# 2001A.net
KiCad netlist of a schematic drawn in Altium Designer
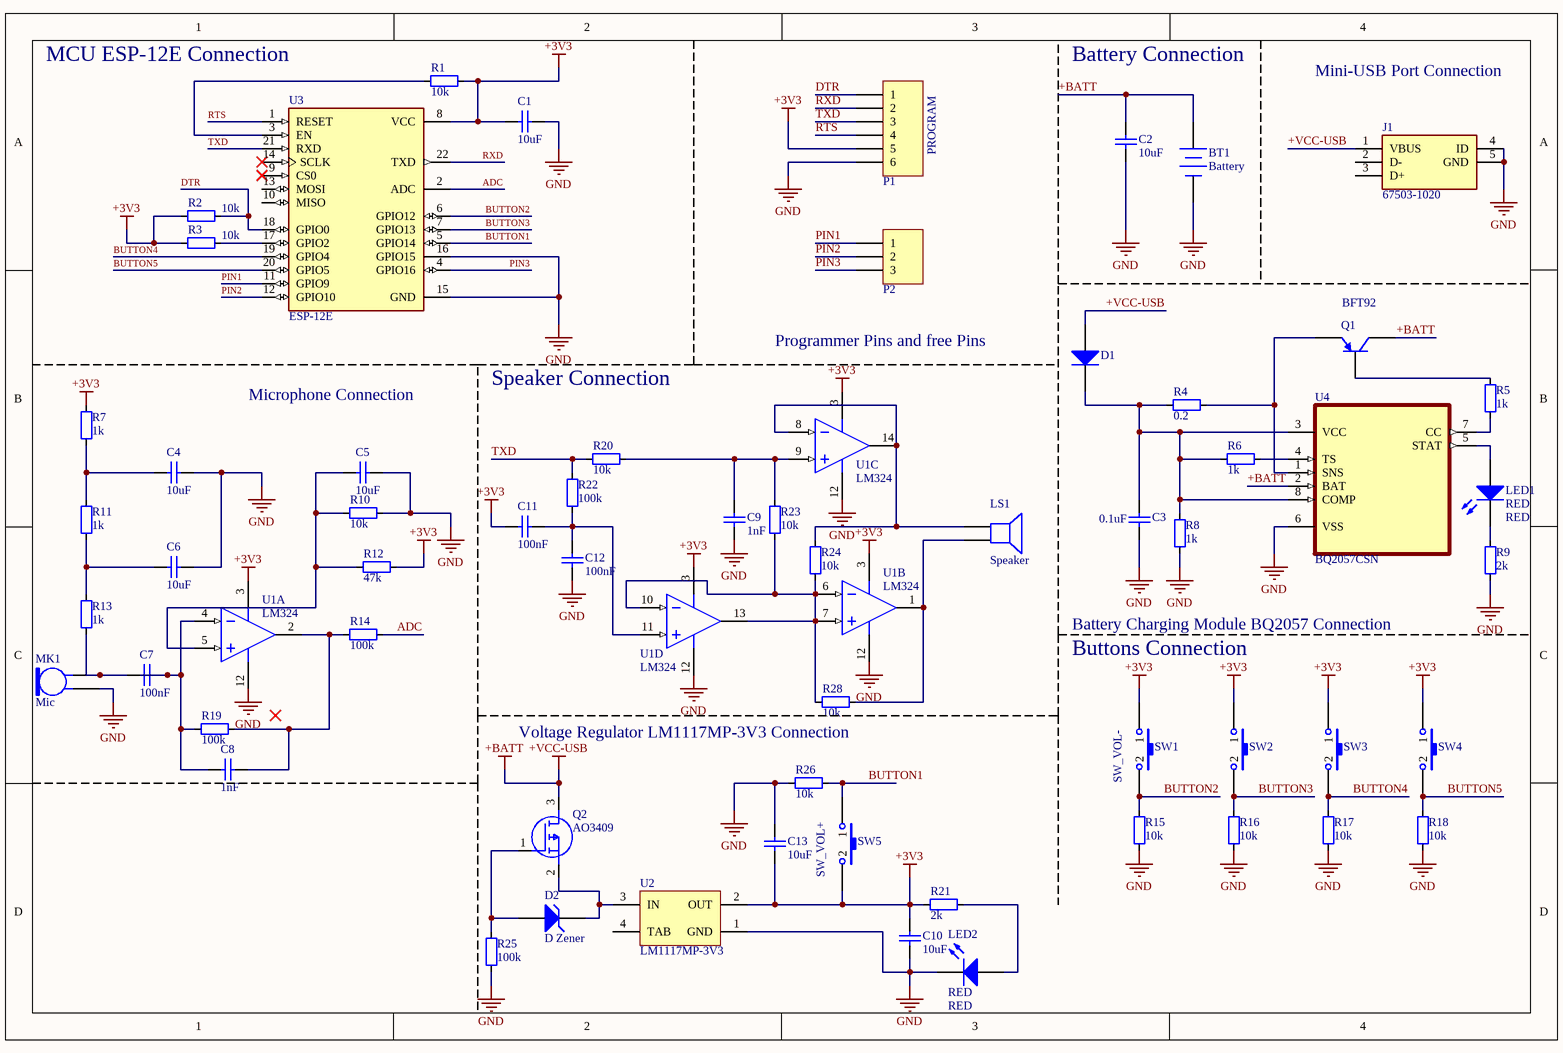
[diagram p0: 2001A.SchDoc]

(export (version "E")
  (design (tool "Eeschema 10.0.6"))
  (components
    (comp (ref "BT1")
      (value "Battery")
      (footprint "BAT-2")
      (description "Multicell Battery")
      (fields (field (name "PUBLISHER") "Altium Limited"))
      (libsource (lib "Miscellaneous Devices") (part "Battery"))
    )
    (comp (ref "C1")
      (value "10uF")
      (footprint "0603_CAP")
      (description "Ceramic capacitor")
      (fields (field (name "Comment") "Cap"))
      (libsource (lib "biblioteka_schematic") (part "Cap"))
    )
    (comp (ref "C2")
      (value "10uF")
      (footprint "0603_CAP")
      (description "Ceramic capacitor")
      (fields (field (name "Comment") "Cap"))
      (libsource (lib "biblioteka_schematic") (part "Cap"))
    )
    (comp (ref "C3")
      (value "0.1uF")
      (footprint "0603_CAP")
      (description "Ceramic capacitor")
      (fields (field (name "Comment") "Cap"))
      (libsource (lib "biblioteka_schematic") (part "Cap"))
    )
    (comp (ref "C4")
      (value "10uF")
      (footprint "0603_CAP")
      (description "Ceramic capacitor")
      (fields (field (name "Comment") "Cap"))
      (libsource (lib "biblioteka_schematic") (part "Cap"))
    )
    (comp (ref "C5")
      (value "10uF")
      (footprint "0603_CAP")
      (description "Ceramic capacitor")
      (fields (field (name "Comment") "Cap"))
      (libsource (lib "biblioteka_schematic") (part "Cap"))
    )
    (comp (ref "C6")
      (value "10uF")
      (footprint "0603_CAP")
      (description "Ceramic capacitor")
      (fields (field (name "Comment") "Cap"))
      (libsource (lib "biblioteka_schematic") (part "Cap"))
    )
    (comp (ref "C7")
      (value "100nF")
      (footprint "0603_CAP")
      (description "Ceramic capacitor")
      (fields (field (name "Comment") "Cap"))
      (libsource (lib "biblioteka_schematic") (part "Cap"))
    )
    (comp (ref "C8")
      (value "1nF")
      (footprint "0603_CAP")
      (description "Ceramic capacitor")
      (fields (field (name "Comment") "Cap"))
      (libsource (lib "biblioteka_schematic") (part "Cap"))
    )
    (comp (ref "C9")
      (value "1nF")
      (footprint "0603_CAP")
      (description "Ceramic capacitor")
      (fields (field (name "Comment") "Cap"))
      (libsource (lib "biblioteka_schematic") (part "Cap"))
    )
    (comp (ref "C10")
      (value "10uF")
      (footprint "0603_CAP")
      (description "Ceramic capacitor")
      (fields (field (name "Comment") "Cap"))
      (libsource (lib "biblioteka_schematic") (part "Cap"))
    )
    (comp (ref "C11")
      (value "100nF")
      (footprint "0603_CAP")
      (description "Ceramic capacitor")
      (fields (field (name "Comment") "Cap"))
      (libsource (lib "biblioteka_schematic") (part "Cap"))
    )
    (comp (ref "C12")
      (value "100nF")
      (footprint "0603_CAP")
      (description "Ceramic capacitor")
      (fields (field (name "Comment") "Cap"))
      (libsource (lib "biblioteka_schematic") (part "Cap"))
    )
    (comp (ref "C13")
      (value "10uF")
      (footprint "0603_CAP")
      (description "Ceramic capacitor")
      (fields (field (name "Comment") "Cap"))
      (libsource (lib "biblioteka_schematic") (part "Cap"))
    )
    (comp (ref "D1")
      (value "~")
      (footprint "0805_DIODE")
      (description "High-speed diode")
      (libsource (lib "biblioteka_schematic") (part "1N4148"))
    )
    (comp (ref "D2")
      (value "D Zener")
      (footprint "*SOD-123_2_BZT52C4V7(Primary)")
      (description "Zener Diode")
      (fields (field (name "PUBLISHER") "Altium Limited"))
      (libsource (lib "Miscellaneous Devices") (part "D Zener"))
    )
    (comp (ref "ESP-12E")
      (value "U3")
      (footprint "XCVR_ESP8266-12E/ESP-12E")
      (fields (field (name "MP") "ESP8266-12E/ESP-12E") (field (name "MF") "AI-Thinker"))
      (libsource (lib "SnapEDAsch") (part "ESP8266-12E/ESP-12E"))
    )
    (comp (ref "J1")
      (value "67503-1020")
      (footprint "SamacSys:67503-1020")
      (description "Connector")
      (fields (field (name "MOUSER PART NUMBER") "538-67503-1020") (field (name "RS PART NUMBER") "1891440"))
      (libsource (lib "usb_otg") (part "67503-1020"))
    )
    (comp (ref "LED1")
      (value "RED")
      (footprint "LED_THT_RED")
      (description "Light-emitting diode")
      (fields (field (name "COLOR") "RED"))
      (libsource (lib "biblioteka_schematic") (part "LED"))
    )
    (comp (ref "LED2")
      (value "RED")
      (footprint "0603")
      (description "Light-emitting diode")
      (fields (field (name "COLOR") "RED"))
      (libsource (lib "biblioteka_schematic") (part "LED"))
    )
    (comp (ref "LS1")
      (value "Speaker")
      (footprint "PIN2")
      (description "Loudspeaker")
      (fields (field (name "PUBLISHER") "Altium Limited"))
      (libsource (lib "Miscellaneous Devices") (part "Speaker"))
    )
    (comp (ref "MK1")
      (value "Mic")
      (footprint "PIN2")
      (description "Microphone")
      (fields (field (name "PUBLISHER") "Altium Limited"))
      (libsource (lib "Miscellaneous Devices") (part "Mic2"))
    )
    (comp (ref "P1")
      (value "PROGRAM")
      (footprint "HDR1X6")
      (description "Header, 6-Pin")
      (fields (field (name "PUBLISHER") "Altium Limited"))
      (libsource (lib "biblioteka_schematic") (part "HDR1X6"))
    )
    (comp (ref "P2")
      (value "HDR1X3")
      (footprint "HDR1X3")
      (description "Header, 3-Pin")
      (fields (field (name "PUBLISHER") "Altium Limited"))
      (libsource (lib "biblioteka_schematic") (part "HDR1X3"))
    )
    (comp (ref "Q1")
      (value "BFT92")
      (footprint "SOT23-3")
      (description "PNP General Purpose Amplifier")
      (fields (field (name "PUBLISHER") "Altium Limited"))
      (libsource (lib "Miscellaneous Devices") (part "2N3906"))
    )
    (comp (ref "Q2")
      (value "AO3409")
      (footprint "SamacSys:SOT95P237X112-3N")
      (description "MOSFET (P-Channel)")
      (fields
        (field (name "MANUFACTURER_PART_NUMBER") "FDN340P")
        (field (name "MOUSER PART NUMBER") "512-FDN340P")
      )
      (libsource (lib "*") (part "FDN340P"))
    )
    (comp (ref "R1")
      (value "10k")
      (footprint "0603")
      (description "Resistior")
      (libsource (lib "") (part "RES_1"))
    )
    (comp (ref "R2")
      (value "10k")
      (footprint "0603")
      (description "Resistior")
      (libsource (lib "") (part "RES_1"))
    )
    (comp (ref "R3")
      (value "10k")
      (footprint "0603")
      (description "Resistior")
      (libsource (lib "") (part "RES_1"))
    )
    (comp (ref "R4")
      (value "0.2")
      (footprint "0805")
      (description "Resistior")
      (libsource (lib "") (part "RES_1"))
    )
    (comp (ref "R5")
      (value "1k")
      (footprint "0603")
      (description "Resistior")
      (libsource (lib "biblioteka_schematic") (part "RES"))
    )
    (comp (ref "R6")
      (value "1k")
      (footprint "0603")
      (description "Resistior")
      (libsource (lib "") (part "RES_1"))
    )
    (comp (ref "R7")
      (value "1k")
      (footprint "0603")
      (description "Resistior")
      (libsource (lib "biblioteka_schematic") (part "RES"))
    )
    (comp (ref "R8")
      (value "1k")
      (footprint "0603")
      (description "Resistior")
      (libsource (lib "biblioteka_schematic") (part "RES"))
    )
    (comp (ref "R9")
      (value "2k")
      (footprint "0603")
      (description "Resistior")
      (libsource (lib "biblioteka_schematic") (part "RES"))
    )
    (comp (ref "R10")
      (value "10k")
      (footprint "0603")
      (description "Resistior")
      (libsource (lib "") (part "RES_1"))
    )
    (comp (ref "R11")
      (value "1k")
      (footprint "0603")
      (description "Resistior")
      (libsource (lib "biblioteka_schematic") (part "RES"))
    )
    (comp (ref "R12")
      (value "47k")
      (footprint "0603")
      (description "Resistior")
      (libsource (lib "") (part "RES_1"))
    )
    (comp (ref "R13")
      (value "1k")
      (footprint "0603")
      (description "Resistior")
      (libsource (lib "biblioteka_schematic") (part "RES"))
    )
    (comp (ref "R14")
      (value "100k")
      (footprint "0603")
      (description "Resistior")
      (libsource (lib "") (part "RES_1"))
    )
    (comp (ref "R15")
      (value "10k")
      (footprint "0603")
      (description "Resistior")
      (libsource (lib "biblioteka_schematic") (part "RES"))
    )
    (comp (ref "R16")
      (value "10k")
      (footprint "0603")
      (description "Resistior")
      (libsource (lib "biblioteka_schematic") (part "RES"))
    )
    (comp (ref "R17")
      (value "10k")
      (footprint "0603")
      (description "Resistior")
      (libsource (lib "biblioteka_schematic") (part "RES"))
    )
    (comp (ref "R18")
      (value "10k")
      (footprint "0603")
      (description "Resistior")
      (libsource (lib "biblioteka_schematic") (part "RES"))
    )
    (comp (ref "R19")
      (value "100k")
      (footprint "0603")
      (description "Resistior")
      (libsource (lib "") (part "RES_1"))
    )
    (comp (ref "R20")
      (value "10k")
      (footprint "0603")
      (description "Resistior")
      (libsource (lib "") (part "RES_1"))
    )
    (comp (ref "R21")
      (value "2k")
      (footprint "0603")
      (description "Resistior")
      (libsource (lib "") (part "RES_3"))
    )
    (comp (ref "R22")
      (value "100k")
      (footprint "0603")
      (description "Resistior")
      (libsource (lib "") (part "RES_2"))
    )
    (comp (ref "R23")
      (value "10k")
      (footprint "0603")
      (description "Resistior")
      (libsource (lib "") (part "RES_2"))
    )
    (comp (ref "R24")
      (value "10k")
      (footprint "0603")
      (description "Resistior")
      (libsource (lib "") (part "RES_2"))
    )
    (comp (ref "R25")
      (value "100k")
      (footprint "0603")
      (description "Resistior")
      (libsource (lib "biblioteka_schematic") (part "RES"))
    )
    (comp (ref "R26")
      (value "10k")
      (footprint "0603")
      (description "Resistior")
      (libsource (lib "") (part "RES_3"))
    )
    (comp (ref "R28")
      (value "10k")
      (footprint "0603")
      (description "Resistior")
      (libsource (lib "") (part "RES_1"))
    )
    (comp (ref "SW1")
      (value "SW_VOL-")
      (footprint "Micro_Switch")
      (description "Switch")
      (fields (field (name "PUBLISHER") "Altium Limited"))
      (libsource (lib "biblioteka_schematic") (part "Micro_Switch"))
    )
    (comp (ref "SW2")
      (value "SW_VOL-")
      (footprint "Micro_Switch")
      (description "Switch")
      (fields (field (name "PUBLISHER") "Altium Limited"))
      (libsource (lib "biblioteka_schematic") (part "Micro_Switch"))
    )
    (comp (ref "SW3")
      (value "SW_VOL-")
      (footprint "Micro_Switch")
      (description "Switch")
      (fields (field (name "PUBLISHER") "Altium Limited"))
      (libsource (lib "biblioteka_schematic") (part "Micro_Switch"))
    )
    (comp (ref "SW4")
      (value "SW_VOL-")
      (footprint "Micro_Switch")
      (description "Switch")
      (fields (field (name "PUBLISHER") "Altium Limited"))
      (libsource (lib "biblioteka_schematic") (part "Micro_Switch"))
    )
    (comp (ref "SW5")
      (value "SW_VOL+")
      (footprint "Micro_Switch")
      (description "Switch")
      (fields (field (name "PUBLISHER") "Altium Limited"))
      (libsource (lib "biblioteka_schematic") (part "Micro_Switch"))
    )
    (comp (ref "U1")
      (value "LM324")
      (footprint "SOIC14")
      (description "Quad Single-Supply Comparator")
      (fields (field (name "PUBLISHER") "Altium Limited"))
      (libsource (lib "biblioteka_schematic") (part "LM339AD"))
    )
    (comp (ref "U2")
      (value "LM1117MP-3V3")
      (footprint "SOT223")
      (description "800mA Low-Dropout Linear Regulator")
      (fields
        (field (name "PARTNUMBER") "LM1117MP-3.3")
        (field (name "MANUFACTURER") "National Semiconductor")
        (field (name "PUBLISHER") "Altium Limited")
      )
      (libsource (lib "biblioteka_schematic") (part "LM1117MP-3V3"))
    )
    (comp (ref "U4")
      (value "BQ2057CSN")
      (footprint "SOIC127P600X175-14N")
      (description "Charger IC Lithium Ion/Polymer 8-SOIC")
      (fields (field (name "MF") "Texas Instruments"))
      (libsource (lib "BQ2057CSN") (part "BQ2057CSN"))
    )
  )
  (nets
    (net (code "1") (name "+3V3") (class "Default")
      (node (ref "C1") (pin "1") (pinfunction "1_1") (pintype "passive"))
      (node (ref "C10") (pin "2") (pinfunction "2_2") (pintype "passive"))
      (node (ref "C11") (pin "1") (pinfunction "1_1") (pintype "passive"))
      (node (ref "C13") (pin "1") (pinfunction "1_1") (pintype "passive"))
      (node (ref "ESP-12E") (pin "8") (pinfunction "VCC_8") (pintype "power_in"))
      (node (ref "P1") (pin "5") (pinfunction "5_5") (pintype "passive"))
      (node (ref "R1") (pin "2") (pinfunction "2_2") (pintype "passive"))
      (node (ref "R12") (pin "2") (pinfunction "2_2") (pintype "passive"))
      (node (ref "R2") (pin "1") (pinfunction "1_1") (pintype "passive"))
      (node (ref "R21") (pin "2") (pinfunction "2_2") (pintype "passive"))
      (node (ref "R3") (pin "1") (pinfunction "1_1") (pintype "passive"))
      (node (ref "R7") (pin "1") (pinfunction "1_1") (pintype "passive"))
      (node (ref "SW1") (pin "1") (pinfunction "1_1") (pintype "passive"))
      (node (ref "SW2") (pin "1") (pinfunction "1_1") (pintype "passive"))
      (node (ref "SW3") (pin "1") (pinfunction "1_1") (pintype "passive"))
      (node (ref "SW4") (pin "1") (pinfunction "1_1") (pintype "passive"))
      (node (ref "SW5") (pin "2") (pinfunction "2_2") (pintype "passive"))
      (node (ref "U1") (pin "3") (pinfunction "V+_3") (pintype "power_in"))
      (node (ref "U2") (pin "2") (pinfunction "OUT_2") (pintype "power_in"))
    )
    (net (code "2") (name "+BATT") (class "Default")
      (node (ref "BT1") (pin "1") (pinfunction "+_1") (pintype "passive"))
      (node (ref "C2") (pin "2") (pinfunction "2_2") (pintype "passive"))
      (node (ref "D1") (pin "1") (pinfunction "A_1") (pintype "passive"))
      (node (ref "J1") (pin "1") (pinfunction "VBUS_1") (pintype "passive"))
      (node (ref "Q1") (pin "3") (pinfunction "C_3") (pintype "passive"))
      (node (ref "Q2") (pin "3") (pinfunction "D_3") (pintype "passive"))
      (node (ref "U4") (pin "2") (pinfunction "BAT_2") (pintype "input"))
    )
    (net (code "3") (name "/ADC") (class "Default")
      (node (ref "ESP-12E") (pin "2") (pinfunction "ADC_2") (pintype "passive"))
      (node (ref "R14") (pin "2") (pinfunction "2_2") (pintype "passive"))
    )
    (net (code "4") (name "/BUTTON1") (class "Default")
      (node (ref "ESP-12E") (pin "5") (pinfunction "GPIO14_5") (pintype "bidirectional"))
      (node (ref "R26") (pin "1") (pinfunction "1_1") (pintype "passive"))
      (node (ref "SW5") (pin "1") (pinfunction "1_1") (pintype "passive"))
    )
    (net (code "5") (name "/BUTTON2") (class "Default")
      (node (ref "ESP-12E") (pin "6") (pinfunction "GPIO12_6") (pintype "bidirectional"))
      (node (ref "R15") (pin "1") (pinfunction "1_1") (pintype "passive"))
      (node (ref "SW1") (pin "2") (pinfunction "2_2") (pintype "passive"))
    )
    (net (code "6") (name "/BUTTON3") (class "Default")
      (node (ref "ESP-12E") (pin "7") (pinfunction "GPIO13_7") (pintype "bidirectional"))
      (node (ref "R16") (pin "1") (pinfunction "1_1") (pintype "passive"))
      (node (ref "SW2") (pin "2") (pinfunction "2_2") (pintype "passive"))
    )
    (net (code "7") (name "/BUTTON4") (class "Default")
      (node (ref "ESP-12E") (pin "19") (pinfunction "GPIO4_19") (pintype "bidirectional"))
      (node (ref "R17") (pin "1") (pinfunction "1_1") (pintype "passive"))
      (node (ref "SW3") (pin "2") (pinfunction "2_2") (pintype "passive"))
    )
    (net (code "8") (name "/BUTTON5") (class "Default")
      (node (ref "ESP-12E") (pin "20") (pinfunction "GPIO5_20") (pintype "bidirectional"))
      (node (ref "R18") (pin "1") (pinfunction "1_1") (pintype "passive"))
      (node (ref "SW4") (pin "2") (pinfunction "2_2") (pintype "passive"))
    )
    (net (code "9") (name "/DTR") (class "Default")
      (node (ref "ESP-12E") (pin "18") (pinfunction "GPIO0_18") (pintype "bidirectional"))
      (node (ref "P1") (pin "1") (pinfunction "1_1") (pintype "passive"))
      (node (ref "R2") (pin "2") (pinfunction "2_2") (pintype "passive"))
    )
    (net (code "10") (name "/PIN1") (class "Default")
      (node (ref "ESP-12E") (pin "11") (pinfunction "GPIO9_11") (pintype "bidirectional"))
      (node (ref "P2") (pin "1") (pinfunction "1_1") (pintype "passive"))
    )
    (net (code "11") (name "/PIN2") (class "Default")
      (node (ref "ESP-12E") (pin "12") (pinfunction "GPIO10_12") (pintype "bidirectional"))
      (node (ref "P2") (pin "2") (pinfunction "2_2") (pintype "passive"))
    )
    (net (code "12") (name "/PIN3") (class "Default")
      (node (ref "ESP-12E") (pin "4") (pinfunction "GPIO16_4") (pintype "bidirectional"))
      (node (ref "P2") (pin "3") (pinfunction "3_3") (pintype "passive"))
    )
    (net (code "13") (name "/RTS") (class "Default")
      (node (ref "ESP-12E") (pin "1") (pinfunction "RESET_1") (pintype "input"))
      (node (ref "P1") (pin "4") (pinfunction "4_4") (pintype "passive"))
    )
    (net (code "14") (name "/RXD") (class "Default")
      (node (ref "ESP-12E") (pin "22") (pinfunction "TXD_22") (pintype "output"))
      (node (ref "P1") (pin "2") (pinfunction "2_2") (pintype "passive"))
    )
    (net (code "15") (name "/TXD") (class "Default")
      (node (ref "ESP-12E") (pin "21") (pinfunction "RXD_21") (pintype "input"))
      (node (ref "P1") (pin "3") (pinfunction "3_3") (pintype "passive"))
      (node (ref "R20") (pin "1") (pinfunction "1_1") (pintype "passive"))
      (node (ref "R22") (pin "2") (pinfunction "2_2") (pintype "passive"))
    )
    (net (code "16") (name "GND") (class "Default")
      (node (ref "BT1") (pin "2") (pinfunction "-_2") (pintype "passive"))
      (node (ref "C1") (pin "2") (pinfunction "2_2") (pintype "passive"))
      (node (ref "C10") (pin "1") (pinfunction "1_1") (pintype "passive"))
      (node (ref "C12") (pin "1") (pinfunction "1_1") (pintype "passive"))
      (node (ref "C13") (pin "2") (pinfunction "2_2") (pintype "passive"))
      (node (ref "C2") (pin "1") (pinfunction "1_1") (pintype "passive"))
      (node (ref "C3") (pin "1") (pinfunction "1_1") (pintype "passive"))
      (node (ref "C4") (pin "2") (pinfunction "2_2") (pintype "passive"))
      (node (ref "C5") (pin "2") (pinfunction "2_2") (pintype "passive"))
      (node (ref "C6") (pin "2") (pinfunction "2_2") (pintype "passive"))
      (node (ref "C9") (pin "1") (pinfunction "1_1") (pintype "passive"))
      (node (ref "ESP-12E") (pin "15") (pinfunction "GND_15") (pintype "power_in"))
      (node (ref "ESP-12E") (pin "16") (pinfunction "GPIO15_16") (pintype "power_in"))
      (node (ref "J1") (pin "4") (pinfunction "ID_4") (pintype "passive"))
      (node (ref "J1") (pin "5") (pinfunction "GND_5") (pintype "passive"))
      (node (ref "LED2") (pin "2") (pinfunction "K_2") (pintype "passive"))
      (node (ref "MK1") (pin "1") (pinfunction "1_1") (pintype "passive"))
      (node (ref "P1") (pin "6") (pinfunction "6_6") (pintype "passive"))
      (node (ref "R10") (pin "2") (pinfunction "2_2") (pintype "passive"))
      (node (ref "R15") (pin "2") (pinfunction "2_2") (pintype "passive"))
      (node (ref "R16") (pin "2") (pinfunction "2_2") (pintype "passive"))
      (node (ref "R17") (pin "2") (pinfunction "2_2") (pintype "passive"))
      (node (ref "R18") (pin "2") (pinfunction "2_2") (pintype "passive"))
      (node (ref "R25") (pin "2") (pinfunction "2_2") (pintype "passive"))
      (node (ref "R26") (pin "2") (pinfunction "2_2") (pintype "passive"))
      (node (ref "R8") (pin "2") (pinfunction "2_2") (pintype "passive"))
      (node (ref "R9") (pin "2") (pinfunction "2_2") (pintype "passive"))
      (node (ref "U1") (pin "12") (pinfunction "GND_12") (pintype "power_in"))
      (node (ref "U2") (pin "1") (pinfunction "GND_1") (pintype "power_in"))
      (node (ref "U4") (pin "6") (pinfunction "VSS_6") (pintype "power_in"))
    )
    (net (code "17") (name "Net-(C4-Pad1)") (class "Default")
      (node (ref "C4") (pin "1") (pinfunction "1_1") (pintype "passive"))
      (node (ref "R11") (pin "1") (pinfunction "1_1") (pintype "passive"))
      (node (ref "R7") (pin "2") (pinfunction "2_2") (pintype "passive"))
    )
    (net (code "18") (name "Net-(C6-Pad1)") (class "Default")
      (node (ref "C6") (pin "1") (pinfunction "1_1") (pintype "passive"))
      (node (ref "R11") (pin "2") (pinfunction "2_2") (pintype "passive"))
      (node (ref "R13") (pin "1") (pinfunction "1_1") (pintype "passive"))
    )
    (net (code "19") (name "Net-(C7-Pad1)") (class "Default")
      (node (ref "C7") (pin "1") (pinfunction "1_1") (pintype "passive"))
      (node (ref "MK1") (pin "2") (pinfunction "2_2") (pintype "passive"))
      (node (ref "R13") (pin "2") (pinfunction "2_2") (pintype "passive"))
    )
    (net (code "20") (name "Net-(D1-K)") (class "Default")
      (node (ref "C3") (pin "2") (pinfunction "2_2") (pintype "passive"))
      (node (ref "D1") (pin "2") (pinfunction "K_2") (pintype "passive"))
      (node (ref "R4") (pin "1") (pinfunction "1_1") (pintype "passive"))
      (node (ref "R6") (pin "1") (pinfunction "1_1") (pintype "passive"))
      (node (ref "R8") (pin "1") (pinfunction "1_1") (pintype "passive"))
      (node (ref "U4") (pin "3") (pinfunction "VCC_3") (pintype "power_in"))
      (node (ref "U4") (pin "8") (pinfunction "COMP_8") (pintype "input"))
    )
    (net (code "21") (name "Net-(D2-A)") (class "Default")
      (node (ref "D2") (pin "1") (pinfunction "A_1") (pintype "passive"))
      (node (ref "Q2") (pin "1") (pinfunction "G_1") (pintype "passive"))
      (node (ref "R25") (pin "1") (pinfunction "1_1") (pintype "passive"))
    )
    (net (code "22") (name "Net-(D2-K)") (class "Default")
      (node (ref "D2") (pin "2") (pinfunction "K_2") (pintype "passive"))
      (node (ref "Q2") (pin "2") (pinfunction "S_2") (pintype "passive"))
      (node (ref "U2") (pin "3") (pinfunction "IN_3") (pintype "power_in"))
    )
    (net (code "23") (name "Net-(ESP-12E-EN)") (class "Default")
      (node (ref "ESP-12E") (pin "3") (pinfunction "EN_3") (pintype "input"))
      (node (ref "R1") (pin "1") (pinfunction "1_1") (pintype "passive"))
    )
    (net (code "24") (name "Net-(ESP-12E-GPIO2)") (class "Default")
      (node (ref "ESP-12E") (pin "17") (pinfunction "GPIO2_17") (pintype "bidirectional"))
      (node (ref "R3") (pin "2") (pinfunction "2_2") (pintype "passive"))
    )
    (net (code "25") (name "Net-(LED1-A)") (class "Default")
      (node (ref "LED1") (pin "1") (pinfunction "A_1") (pintype "passive"))
      (node (ref "U4") (pin "5") (pinfunction "STAT_5") (pintype "output"))
    )
    (net (code "26") (name "Net-(LED1-K)") (class "Default")
      (node (ref "LED1") (pin "2") (pinfunction "K_2") (pintype "passive"))
      (node (ref "R9") (pin "1") (pinfunction "1_1") (pintype "passive"))
    )
    (net (code "27") (name "Net-(LED2-A)") (class "Default")
      (node (ref "LED2") (pin "1") (pinfunction "A_1") (pintype "passive"))
      (node (ref "R21") (pin "1") (pinfunction "1_1") (pintype "passive"))
    )
    (net (code "28") (name "Net-(Q1-B)") (class "Default")
      (node (ref "Q1") (pin "2") (pinfunction "B_2") (pintype "passive"))
      (node (ref "R5") (pin "1") (pinfunction "1_1") (pintype "passive"))
    )
    (net (code "29") (name "Net-(Q1-E)") (class "Default")
      (node (ref "Q1") (pin "1") (pinfunction "E_1") (pintype "passive"))
      (node (ref "R4") (pin "2") (pinfunction "2_2") (pintype "passive"))
      (node (ref "U4") (pin "1") (pinfunction "SNS_1") (pintype "input"))
    )
    (net (code "30") (name "Net-(U1A-IN+)") (class "Default")
      (node (ref "C5") (pin "1") (pinfunction "1_1") (pintype "passive"))
      (node (ref "R10") (pin "1") (pinfunction "1_1") (pintype "passive"))
      (node (ref "R12") (pin "1") (pinfunction "1_1") (pintype "passive"))
      (node (ref "U1") (pin "5") (pinfunction "IN+_5") (pintype "input"))
    )
    (net (code "31") (name "Net-(U1A-IN-)") (class "Default")
      (node (ref "C7") (pin "2") (pinfunction "2_2") (pintype "passive"))
      (node (ref "C8") (pin "1") (pinfunction "1_1") (pintype "passive"))
      (node (ref "R19") (pin "1") (pinfunction "1_1") (pintype "passive"))
      (node (ref "U1") (pin "4") (pinfunction "IN-_4") (pintype "input"))
    )
    (net (code "32") (name "Net-(U1A-OUT)") (class "Default")
      (node (ref "C8") (pin "2") (pinfunction "2_2") (pintype "passive"))
      (node (ref "R14") (pin "1") (pinfunction "1_1") (pintype "passive"))
      (node (ref "R19") (pin "2") (pinfunction "2_2") (pintype "passive"))
      (node (ref "U1") (pin "2") (pinfunction "OUT_2") (pintype "open_collector"))
    )
    (net (code "33") (name "Net-(U1B-IN+)") (class "Default")
      (node (ref "R23") (pin "1") (pinfunction "1_1") (pintype "passive"))
      (node (ref "R24") (pin "1") (pinfunction "1_1") (pintype "passive"))
      (node (ref "R28") (pin "1") (pinfunction "1_1") (pintype "passive"))
      (node (ref "U1") (pin "10") (pinfunction "IN-_10") (pintype "input"))
      (node (ref "U1") (pin "13") (pinfunction "OUT_13") (pintype "open_collector"))
      (node (ref "U1") (pin "6") (pinfunction "IN-_6") (pintype "input"))
      (node (ref "U1") (pin "7") (pinfunction "IN+_7") (pintype "input"))
    )
    (net (code "34") (name "Net-(U1B-OUT)") (class "Default")
      (node (ref "LS1") (pin "2") (pinfunction "2_2") (pintype "passive"))
      (node (ref "R28") (pin "2") (pinfunction "2_2") (pintype "passive"))
      (node (ref "U1") (pin "1") (pinfunction "OUT_1") (pintype "open_collector"))
    )
    (net (code "35") (name "Net-(U1C-IN+)") (class "Default")
      (node (ref "C9") (pin "2") (pinfunction "2_2") (pintype "passive"))
      (node (ref "R20") (pin "2") (pinfunction "2_2") (pintype "passive"))
      (node (ref "R23") (pin "2") (pinfunction "2_2") (pintype "passive"))
      (node (ref "U1") (pin "9") (pinfunction "IN+_9") (pintype "input"))
    )
    (net (code "36") (name "Net-(U1C-IN-)") (class "Default")
      (node (ref "LS1") (pin "1") (pinfunction "1_1") (pintype "passive"))
      (node (ref "R24") (pin "2") (pinfunction "2_2") (pintype "passive"))
      (node (ref "U1") (pin "14") (pinfunction "OUT_14") (pintype "open_collector"))
      (node (ref "U1") (pin "8") (pinfunction "IN-_8") (pintype "input"))
    )
    (net (code "37") (name "Net-(U1D-IN+)") (class "Default")
      (node (ref "C11") (pin "2") (pinfunction "2_2") (pintype "passive"))
      (node (ref "C12") (pin "2") (pinfunction "2_2") (pintype "passive"))
      (node (ref "R22") (pin "1") (pinfunction "1_1") (pintype "passive"))
      (node (ref "U1") (pin "11") (pinfunction "IN+_11") (pintype "input"))
    )
    (net (code "38") (name "Net-(U4-CC)") (class "Default")
      (node (ref "R5") (pin "2") (pinfunction "2_2") (pintype "passive"))
      (node (ref "U4") (pin "7") (pinfunction "CC_7") (pintype "output"))
    )
    (net (code "39") (name "Net-(U4-TS)") (class "Default")
      (node (ref "R6") (pin "2") (pinfunction "2_2") (pintype "passive"))
      (node (ref "U4") (pin "4") (pinfunction "TS_4") (pintype "input"))
    )
    (net (code "40") (name "unconnected-(ESP-12E-CS0-Pad9)") (class "Default")
      (node (ref "ESP-12E") (pin "9") (pinfunction "CS0_9") (pintype "input+no_connect"))
    )
    (net (code "41") (name "unconnected-(ESP-12E-MISO-Pad10)") (class "Default")
      (node (ref "ESP-12E") (pin "10") (pinfunction "MISO_10") (pintype "bidirectional"))
    )
    (net (code "42") (name "unconnected-(ESP-12E-MOSI-Pad13)") (class "Default")
      (node (ref "ESP-12E") (pin "13") (pinfunction "MOSI_13") (pintype "bidirectional"))
    )
    (net (code "43") (name "unconnected-(ESP-12E-SCLK-Pad14)") (class "Default")
      (node (ref "ESP-12E") (pin "14") (pinfunction "SCLK_14") (pintype "input+no_connect"))
    )
    (net (code "44") (name "unconnected-(J1-D+-Pad3)") (class "Default")
      (node (ref "J1") (pin "3") (pinfunction "D+_3") (pintype "passive"))
    )
    (net (code "45") (name "unconnected-(J1-D--Pad2)") (class "Default")
      (node (ref "J1") (pin "2") (pinfunction "D-_2") (pintype "passive"))
    )
    (net (code "46") (name "unconnected-(U2-TAB-Pad4)") (class "Default")
      (node (ref "U2") (pin "4") (pinfunction "TAB_4") (pintype "power_in"))
    )
  )
)
